# TestBoard.net
KiCad netlist of a schematic drawn in EAGLE
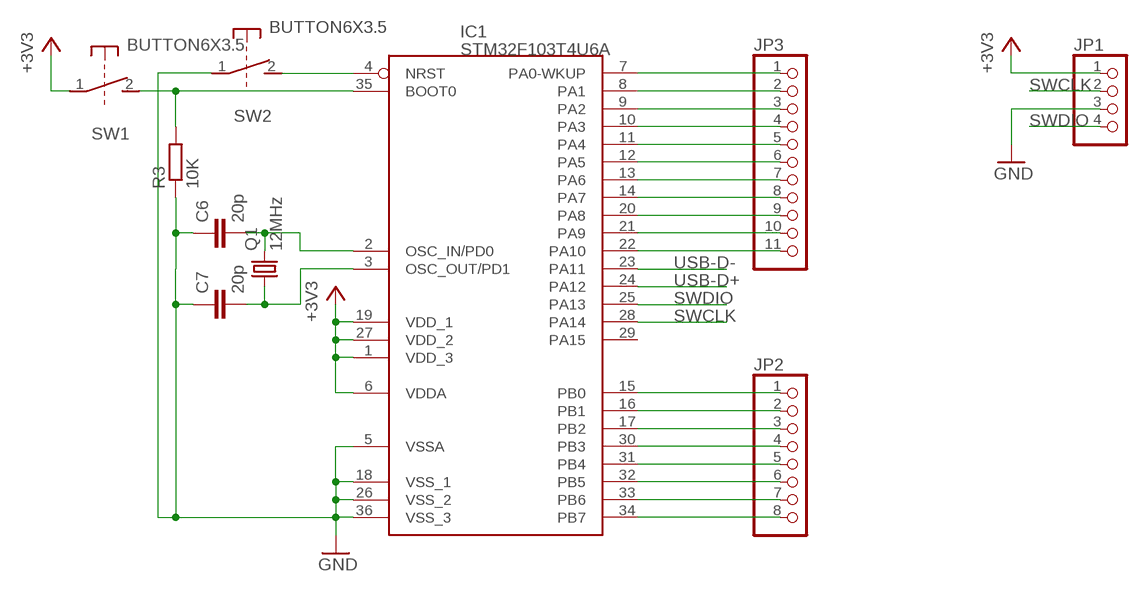
[diagram p0: schematic, sheet 1]
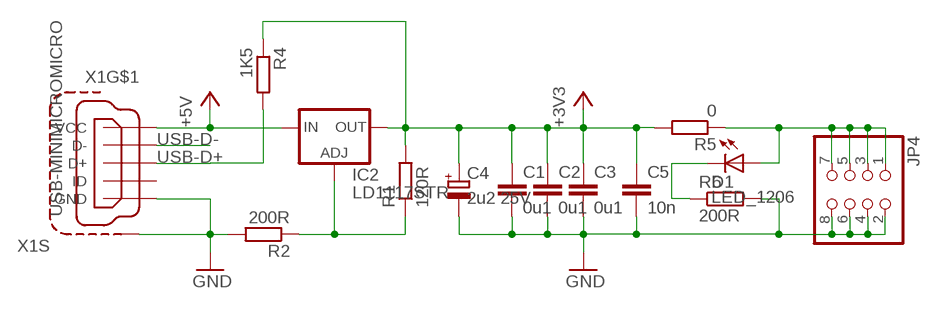
[diagram p1: schematic, sheet 2]

(export (version "E")
  (design (tool "Eeschema 10.0.6"))
  (components
    (comp (ref "C6")
      (value "20p")
      (footprint "eagle-import:CAP0805")
      (libsource (lib "eagle-import") (part "CAP_0805"))
    )
    (comp (ref "C7")
      (value "20p")
      (footprint "eagle-import:CAP0805")
      (libsource (lib "eagle-import") (part "CAP_0805"))
    )
    (comp (ref "IC1")
      (value "STM32F103T4U6A")
      (footprint "eagle-import:QFN50P606X606X100-36")
      (libsource (lib "eagle-import") (part "STM32F103T4U6A"))
    )
    (comp (ref "JP1")
      (value "PINHD-1X4")
      (footprint "eagle-import:1X04")
      (libsource (lib "eagle-import") (part "PINHD-1X4"))
    )
    (comp (ref "JP2")
      (value "PINHD-1X8")
      (footprint "eagle-import:1X08")
      (libsource (lib "eagle-import") (part "PINHD-1X8"))
    )
    (comp (ref "JP3")
      (value "PINHD-1X11")
      (footprint "eagle-import:1X11")
      (libsource (lib "eagle-import") (part "PINHD-1X11"))
    )
    (comp (ref "Q1")
      (value "12MHz")
      (footprint "eagle-import:HC49UP")
      (libsource (lib "eagle-import") (part "CRYSTALHC49UP"))
    )
    (comp (ref "R3")
      (value "10K")
      (footprint "eagle-import:RESC2012X50")
      (libsource (lib "eagle-import") (part "R_R0805"))
    )
    (comp (ref "SW1")
      (value "BUTTON6X3.5")
      (footprint "eagle-import:SW-6X3.5")
      (libsource (lib "eagle-import") (part "BUTTON6X3.5"))
    )
    (comp (ref "SW2")
      (value "BUTTON6X3.5")
      (footprint "eagle-import:SW-6X3.5")
      (libsource (lib "eagle-import") (part "BUTTON6X3.5"))
    )
    (comp (ref "C1")
      (value "0u1")
      (footprint "eagle-import:CAP0805")
      (libsource (lib "eagle-import") (part "CAP_0805"))
    )
    (comp (ref "C2")
      (value "0u1")
      (footprint "eagle-import:CAP0805")
      (libsource (lib "eagle-import") (part "CAP_0805"))
    )
    (comp (ref "C3")
      (value "0u1")
      (footprint "eagle-import:CAP0805")
      (libsource (lib "eagle-import") (part "CAP_0805"))
    )
    (comp (ref "C4")
      (value "2u2 25V")
      (footprint "eagle-import:CAPMP3317X180")
      (libsource (lib "eagle-import") (part "CAP-POL_CAPE3216-A"))
    )
    (comp (ref "C5")
      (value "10n")
      (footprint "eagle-import:CAP0805")
      (libsource (lib "eagle-import") (part "CAP_0805"))
    )
    (comp (ref "D1")
      (value "LED_1206")
      (footprint "eagle-import:LED1206")
      (libsource (lib "eagle-import") (part "LED_1206"))
    )
    (comp (ref "IC2")
      (value "LD1117STR")
      (footprint "eagle-import:SOT230P700X180-4")
      (libsource (lib "eagle-import") (part "VREG-ADJLD1117S"))
    )
    (comp (ref "JP4")
      (value "PINHD-2X4")
      (footprint "eagle-import:2X04")
      (libsource (lib "eagle-import") (part "PINHD-2X4"))
    )
    (comp (ref "R1")
      (value "120R")
      (footprint "eagle-import:RESC2012X50")
      (libsource (lib "eagle-import") (part "R_R0805"))
    )
    (comp (ref "R2")
      (value "200R")
      (footprint "eagle-import:RESC2012X50")
      (libsource (lib "eagle-import") (part "R_R0805"))
    )
    (comp (ref "R4")
      (value "1K5")
      (footprint "eagle-import:RESC2012X50")
      (libsource (lib "eagle-import") (part "R_R0805"))
    )
    (comp (ref "R5")
      (value "0")
      (footprint "eagle-import:RESC2012X50")
      (libsource (lib "eagle-import") (part "R_R0805"))
    )
    (comp (ref "R6")
      (value "200R")
      (footprint "eagle-import:RESC2012X50")
      (libsource (lib "eagle-import") (part "R_R0805"))
    )
    (comp (ref "X1")
      (value "USB-MINIMICROMICRO")
      (footprint "eagle-import:USB-B-MICRO-SMD")
      (libsource (lib "eagle-import") (part "USB-MINIMICROMICRO"))
    )
  )
  (nets
    (net (code "1") (name "+3V3") (class "Default")
      (node (ref "C1") (pin "1") (pinfunction "1_1") (pintype "passive"))
      (node (ref "C2") (pin "1") (pinfunction "1_1") (pintype "passive"))
      (node (ref "C3") (pin "1") (pinfunction "1_1") (pintype "passive"))
      (node (ref "C4") (pin "1") (pinfunction "+_1") (pintype "passive"))
      (node (ref "C5") (pin "1") (pinfunction "1_1") (pintype "passive"))
      (node (ref "IC1") (pin "1") (pinfunction "VDD_3_1") (pintype "power_in"))
      (node (ref "IC1") (pin "19") (pinfunction "VDD_1_19") (pintype "power_in"))
      (node (ref "IC1") (pin "27") (pinfunction "VDD_2_27") (pintype "power_in"))
      (node (ref "IC1") (pin "6") (pinfunction "VDDA_6") (pintype "power_in"))
      (node (ref "IC2") (pin "2") (pinfunction "OUT_2") (pintype "passive"))
      (node (ref "IC2") (pin "4") (pinfunction "OUT_4") (pintype "passive"))
      (node (ref "JP1") (pin "1") (pinfunction "1_1") (pintype "passive"))
      (node (ref "R1") (pin "2") (pinfunction "2_2") (pintype "passive"))
      (node (ref "R4") (pin "1") (pinfunction "1_1") (pintype "passive"))
      (node (ref "R5") (pin "2") (pinfunction "2_2") (pintype "passive"))
      (node (ref "SW1") (pin "1") (pinfunction "1_1") (pintype "passive"))
    )
    (net (code "2") (name "+5V") (class "Default")
      (node (ref "IC2") (pin "3") (pinfunction "IN_3") (pintype "input"))
      (node (ref "X1") (pin "VBUS") (pinfunction "VCC_VBUS") (pintype "passive"))
    )
    (net (code "3") (name "GND") (class "Default")
      (node (ref "C1") (pin "2") (pinfunction "2_2") (pintype "passive"))
      (node (ref "C2") (pin "2") (pinfunction "2_2") (pintype "passive"))
      (node (ref "C3") (pin "2") (pinfunction "2_2") (pintype "passive"))
      (node (ref "C4") (pin "2") (pinfunction "-_2") (pintype "passive"))
      (node (ref "C5") (pin "2") (pinfunction "2_2") (pintype "passive"))
      (node (ref "C6") (pin "1") (pinfunction "1_1") (pintype "passive"))
      (node (ref "C7") (pin "1") (pinfunction "1_1") (pintype "passive"))
      (node (ref "IC1") (pin "18") (pinfunction "VSS_1_18") (pintype "power_in"))
      (node (ref "IC1") (pin "26") (pinfunction "VSS_2_26") (pintype "power_in"))
      (node (ref "IC1") (pin "36") (pinfunction "VSS_3_36") (pintype "power_in"))
      (node (ref "IC1") (pin "5") (pinfunction "VSSA_5") (pintype "power_in"))
      (node (ref "JP1") (pin "3") (pinfunction "3_3") (pintype "passive"))
      (node (ref "JP4") (pin "2") (pinfunction "2_2") (pintype "passive"))
      (node (ref "JP4") (pin "4") (pinfunction "4_4") (pintype "passive"))
      (node (ref "JP4") (pin "6") (pinfunction "6_6") (pintype "passive"))
      (node (ref "JP4") (pin "8") (pinfunction "8_8") (pintype "passive"))
      (node (ref "R2") (pin "2") (pinfunction "2_2") (pintype "passive"))
      (node (ref "R3") (pin "1") (pinfunction "1_1") (pintype "passive"))
      (node (ref "R6") (pin "2") (pinfunction "2_2") (pintype "passive"))
      (node (ref "SW2") (pin "1") (pinfunction "1_1") (pintype "passive"))
      (node (ref "X1") (pin "GND") (pinfunction "GND_GND") (pintype "passive"))
      (node (ref "X1") (pin "SHIELD1") (pinfunction "S1_SHIELD1") (pintype "passive"))
      (node (ref "X1") (pin "SHIELD2") (pinfunction "S1_SHIELD2") (pintype "passive"))
      (node (ref "X1") (pin "SHIELD3") (pinfunction "S1_SHIELD3") (pintype "passive"))
    )
    (net (code "4") (name "Net-(D1-PadA)") (class "Default")
      (node (ref "D1") (pin "A") (pinfunction "A_A") (pintype "passive"))
      (node (ref "JP4") (pin "1") (pinfunction "1_1") (pintype "passive"))
      (node (ref "JP4") (pin "3") (pinfunction "3_3") (pintype "passive"))
      (node (ref "JP4") (pin "5") (pinfunction "5_5") (pintype "passive"))
      (node (ref "JP4") (pin "7") (pinfunction "7_7") (pintype "passive"))
      (node (ref "R5") (pin "1") (pinfunction "1_1") (pintype "passive"))
    )
    (net (code "5") (name "Net-(D1-PadC)") (class "Default")
      (node (ref "D1") (pin "C") (pinfunction "C_C") (pintype "passive"))
      (node (ref "R6") (pin "1") (pinfunction "1_1") (pintype "passive"))
    )
    (net (code "6") (name "Net-(IC1-BOOT0)") (class "Default")
      (node (ref "IC1") (pin "35") (pinfunction "BOOT0_35") (pintype "bidirectional"))
      (node (ref "R3") (pin "2") (pinfunction "2_2") (pintype "passive"))
      (node (ref "SW1") (pin "2") (pinfunction "2_2") (pintype "passive"))
    )
    (net (code "7") (name "Net-(IC1-NRST)") (class "Default")
      (node (ref "IC1") (pin "4") (pinfunction "NRST_4") (pintype "bidirectional"))
      (node (ref "SW2") (pin "2") (pinfunction "2_2") (pintype "passive"))
    )
    (net (code "8") (name "Net-(IC1-OSC_IN{slash}PD0)") (class "Default")
      (node (ref "C6") (pin "2") (pinfunction "2_2") (pintype "passive"))
      (node (ref "IC1") (pin "2") (pinfunction "OSC_IN/PD0_2") (pintype "bidirectional"))
      (node (ref "Q1") (pin "2") (pinfunction "2_2") (pintype "passive"))
    )
    (net (code "9") (name "Net-(IC1-OSC_OUT{slash}PD1)") (class "Default")
      (node (ref "C7") (pin "2") (pinfunction "2_2") (pintype "passive"))
      (node (ref "IC1") (pin "3") (pinfunction "OSC_OUT/PD1_3") (pintype "bidirectional"))
      (node (ref "Q1") (pin "1") (pinfunction "1_1") (pintype "passive"))
    )
    (net (code "10") (name "Net-(IC1-PA0-WKUP)") (class "Default")
      (node (ref "IC1") (pin "7") (pinfunction "PA0-WKUP_7") (pintype "bidirectional"))
      (node (ref "JP3") (pin "1") (pinfunction "1_1") (pintype "passive"))
    )
    (net (code "11") (name "Net-(IC1-PA1)") (class "Default")
      (node (ref "IC1") (pin "8") (pinfunction "PA1_8") (pintype "bidirectional"))
      (node (ref "JP3") (pin "2") (pinfunction "2_2") (pintype "passive"))
    )
    (net (code "12") (name "Net-(IC1-PA2)") (class "Default")
      (node (ref "IC1") (pin "9") (pinfunction "PA2_9") (pintype "bidirectional"))
      (node (ref "JP3") (pin "3") (pinfunction "3_3") (pintype "passive"))
    )
    (net (code "13") (name "Net-(IC1-PA3)") (class "Default")
      (node (ref "IC1") (pin "10") (pinfunction "PA3_10") (pintype "bidirectional"))
      (node (ref "JP3") (pin "4") (pinfunction "4_4") (pintype "passive"))
    )
    (net (code "14") (name "Net-(IC1-PA4)") (class "Default")
      (node (ref "IC1") (pin "11") (pinfunction "PA4_11") (pintype "bidirectional"))
      (node (ref "JP3") (pin "5") (pinfunction "5_5") (pintype "passive"))
    )
    (net (code "15") (name "Net-(IC1-PA5)") (class "Default")
      (node (ref "IC1") (pin "12") (pinfunction "PA5_12") (pintype "bidirectional"))
      (node (ref "JP3") (pin "6") (pinfunction "6_6") (pintype "passive"))
    )
    (net (code "16") (name "Net-(IC1-PA6)") (class "Default")
      (node (ref "IC1") (pin "13") (pinfunction "PA6_13") (pintype "bidirectional"))
      (node (ref "JP3") (pin "7") (pinfunction "7_7") (pintype "passive"))
    )
    (net (code "17") (name "Net-(IC1-PA7)") (class "Default")
      (node (ref "IC1") (pin "14") (pinfunction "PA7_14") (pintype "bidirectional"))
      (node (ref "JP3") (pin "8") (pinfunction "8_8") (pintype "passive"))
    )
    (net (code "18") (name "Net-(IC1-PA8)") (class "Default")
      (node (ref "IC1") (pin "20") (pinfunction "PA8_20") (pintype "bidirectional"))
      (node (ref "JP3") (pin "9") (pinfunction "9_9") (pintype "passive"))
    )
    (net (code "19") (name "Net-(IC1-PA9)") (class "Default")
      (node (ref "IC1") (pin "21") (pinfunction "PA9_21") (pintype "bidirectional"))
      (node (ref "JP3") (pin "10") (pinfunction "10_10") (pintype "passive"))
    )
    (net (code "20") (name "Net-(IC1-PA10)") (class "Default")
      (node (ref "IC1") (pin "22") (pinfunction "PA10_22") (pintype "bidirectional"))
      (node (ref "JP3") (pin "11") (pinfunction "11_11") (pintype "passive"))
    )
    (net (code "21") (name "Net-(IC1-PB0)") (class "Default")
      (node (ref "IC1") (pin "15") (pinfunction "PB0_15") (pintype "bidirectional"))
      (node (ref "JP2") (pin "1") (pinfunction "1_1") (pintype "passive"))
    )
    (net (code "22") (name "Net-(IC1-PB1)") (class "Default")
      (node (ref "IC1") (pin "16") (pinfunction "PB1_16") (pintype "bidirectional"))
      (node (ref "JP2") (pin "2") (pinfunction "2_2") (pintype "passive"))
    )
    (net (code "23") (name "Net-(IC1-PB2)") (class "Default")
      (node (ref "IC1") (pin "17") (pinfunction "PB2_17") (pintype "bidirectional"))
      (node (ref "JP2") (pin "3") (pinfunction "3_3") (pintype "passive"))
    )
    (net (code "24") (name "Net-(IC1-PB3)") (class "Default")
      (node (ref "IC1") (pin "30") (pinfunction "PB3_30") (pintype "bidirectional"))
      (node (ref "JP2") (pin "4") (pinfunction "4_4") (pintype "passive"))
    )
    (net (code "25") (name "Net-(IC1-PB4)") (class "Default")
      (node (ref "IC1") (pin "31") (pinfunction "PB4_31") (pintype "bidirectional"))
      (node (ref "JP2") (pin "5") (pinfunction "5_5") (pintype "passive"))
    )
    (net (code "26") (name "Net-(IC1-PB5)") (class "Default")
      (node (ref "IC1") (pin "32") (pinfunction "PB5_32") (pintype "bidirectional"))
      (node (ref "JP2") (pin "6") (pinfunction "6_6") (pintype "passive"))
    )
    (net (code "27") (name "Net-(IC1-PB6)") (class "Default")
      (node (ref "IC1") (pin "33") (pinfunction "PB6_33") (pintype "bidirectional"))
      (node (ref "JP2") (pin "7") (pinfunction "7_7") (pintype "passive"))
    )
    (net (code "28") (name "Net-(IC1-PB7)") (class "Default")
      (node (ref "IC1") (pin "34") (pinfunction "PB7_34") (pintype "bidirectional"))
      (node (ref "JP2") (pin "8") (pinfunction "8_8") (pintype "passive"))
    )
    (net (code "29") (name "Net-(IC2-ADJ)") (class "Default")
      (node (ref "IC2") (pin "1") (pinfunction "ADJ_1") (pintype "input"))
      (node (ref "R1") (pin "1") (pinfunction "1_1") (pintype "passive"))
      (node (ref "R2") (pin "1") (pinfunction "1_1") (pintype "passive"))
    )
    (net (code "30") (name "SWCLK") (class "Default")
      (node (ref "IC1") (pin "28") (pinfunction "PA14_28") (pintype "bidirectional"))
      (node (ref "JP1") (pin "2") (pinfunction "2_2") (pintype "passive"))
    )
    (net (code "31") (name "SWDIO") (class "Default")
      (node (ref "IC1") (pin "25") (pinfunction "PA13_25") (pintype "bidirectional"))
      (node (ref "JP1") (pin "4") (pinfunction "4_4") (pintype "passive"))
    )
    (net (code "32") (name "USB-D+") (class "Default")
      (node (ref "IC1") (pin "24") (pinfunction "PA12_24") (pintype "bidirectional"))
      (node (ref "R4") (pin "2") (pinfunction "2_2") (pintype "passive"))
      (node (ref "X1") (pin "D+") (pinfunction "D+_D+") (pintype "passive"))
    )
    (net (code "33") (name "USB-D-") (class "Default")
      (node (ref "IC1") (pin "23") (pinfunction "PA11_23") (pintype "bidirectional"))
      (node (ref "X1") (pin "D-") (pinfunction "D-_D-") (pintype "passive"))
    )
    (net (code "34") (name "unconnected-(IC1-PA15-Pad29)") (class "Default")
      (node (ref "IC1") (pin "29") (pinfunction "PA15_29") (pintype "bidirectional"))
    )
    (net (code "35") (name "unconnected-(X1-PadID)") (class "Default")
      (node (ref "X1") (pin "ID") (pinfunction "ID_ID") (pintype "passive"))
    )
  )
)
